# Demo_PCB.net
KiCad netlist of a schematic drawn in EAGLE
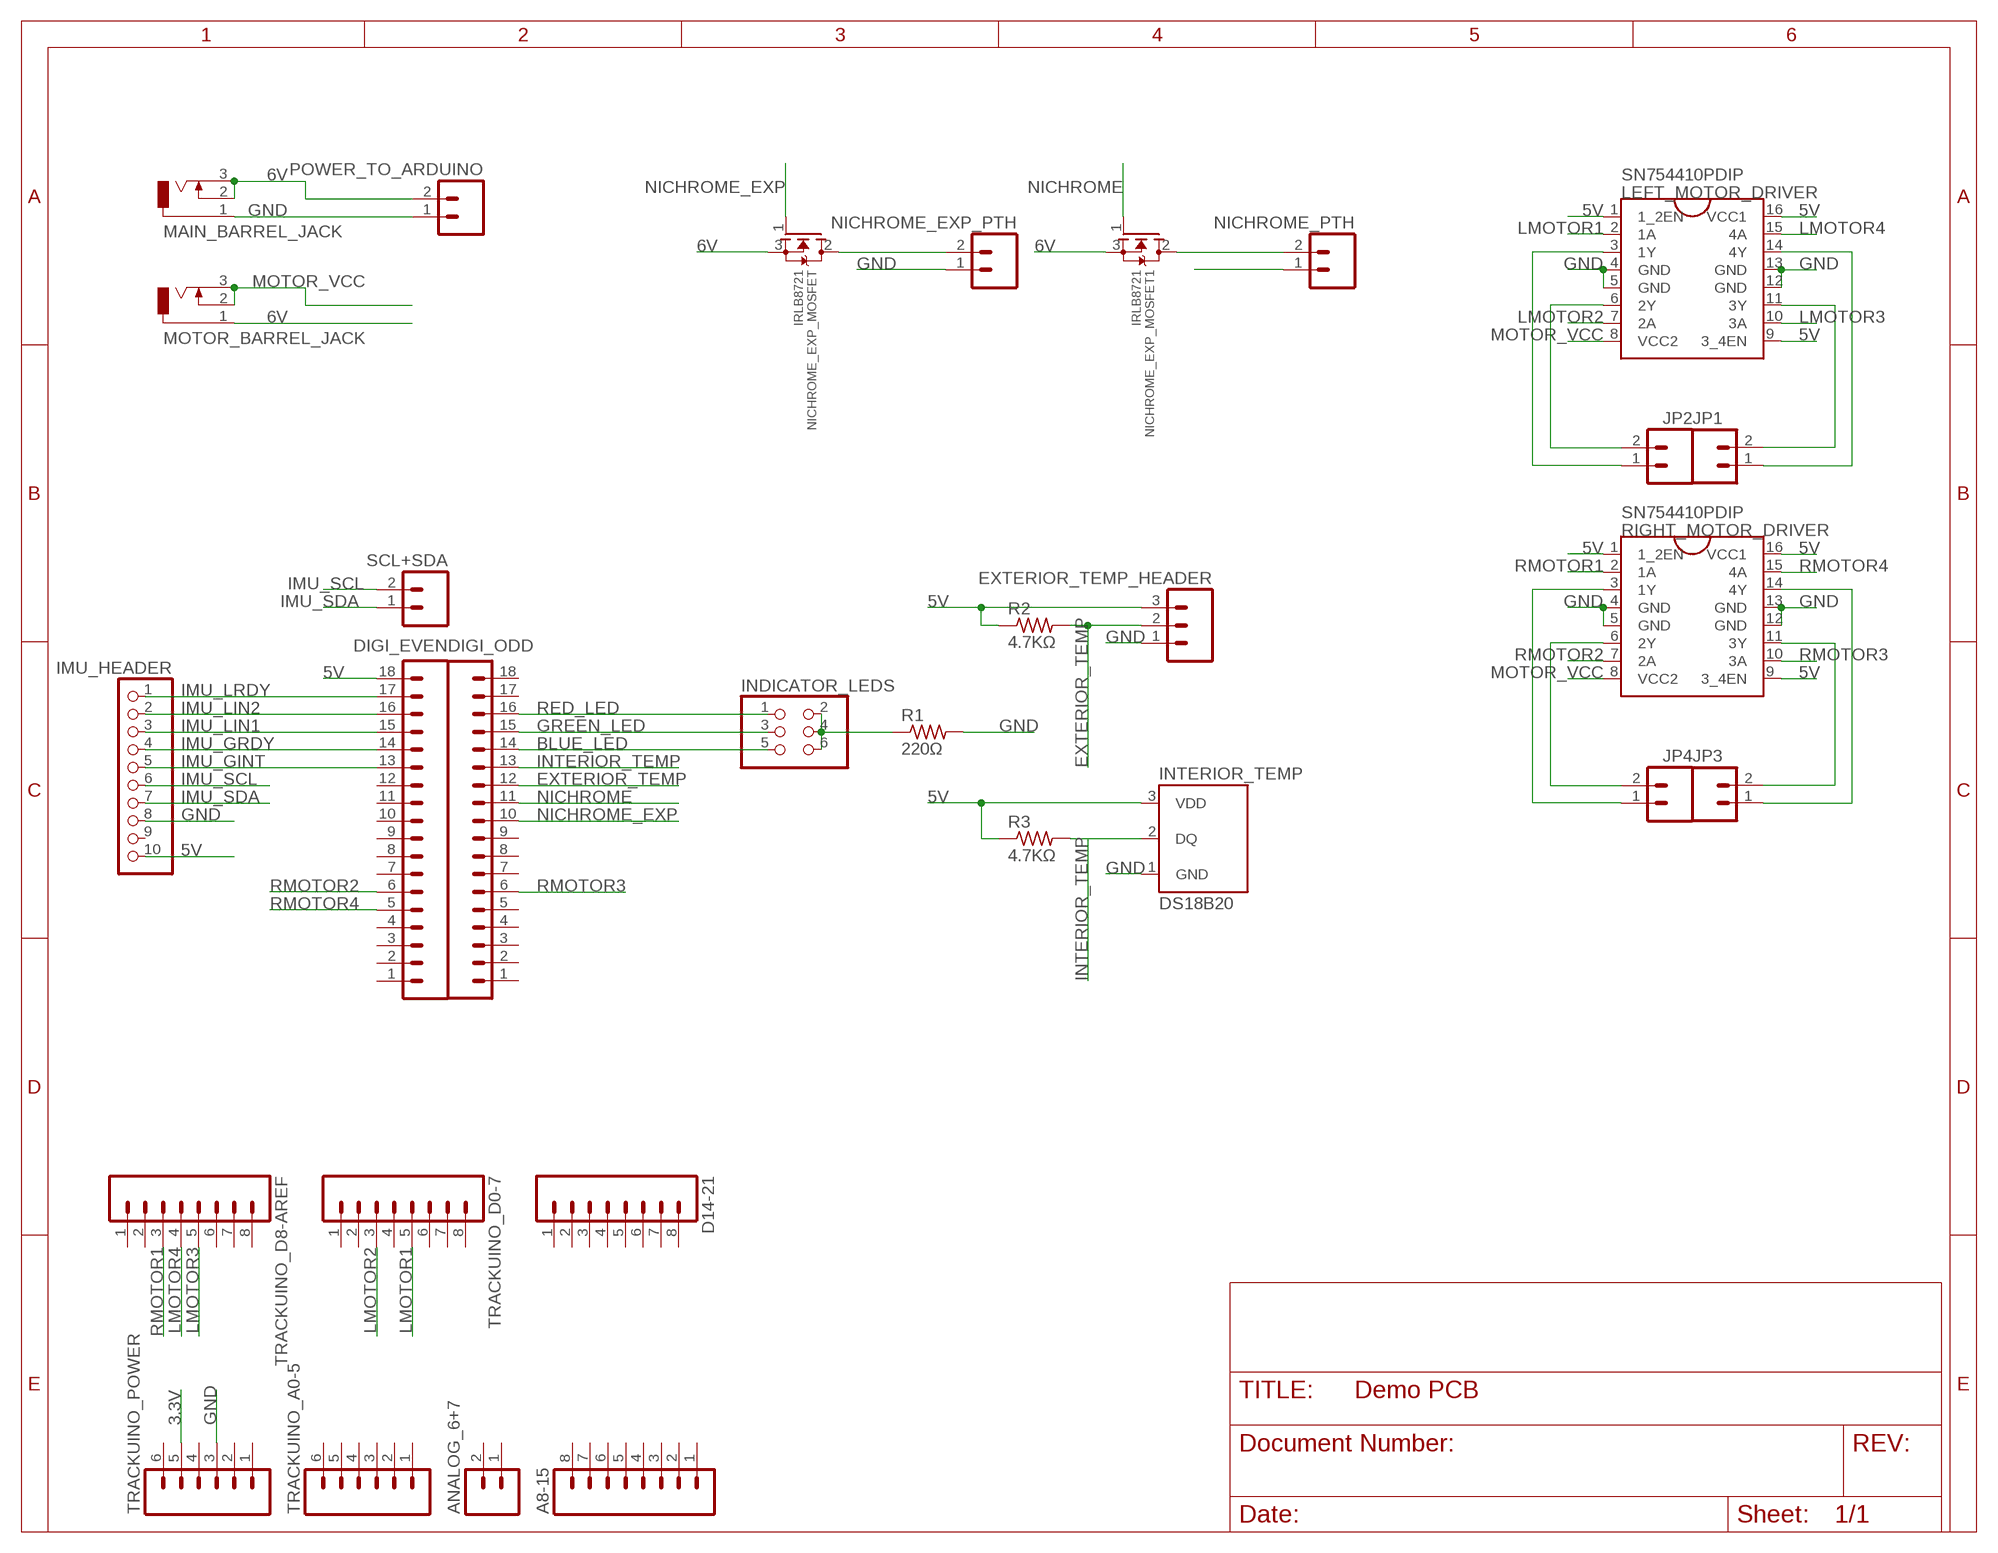
[diagram p0: schematic, sheet 1]

(export (version "E")
  (design (tool "Eeschema 10.0.6"))
  (components
    (comp (ref "A8-15")
      (value "M08")
      (footprint "eagle-import:1X08_ROUND")
      (libsource (lib "eagle-import") (part "M08"))
    )
    (comp (ref "ANALOG_6+7")
      (value "M02PTH")
      (footprint "eagle-import:1X02")
      (libsource (lib "eagle-import") (part "M02PTH"))
    )
    (comp (ref "D14-21")
      (value "M08")
      (footprint "eagle-import:1X08_ROUND")
      (libsource (lib "eagle-import") (part "M08"))
    )
    (comp (ref "DIGI_EVEN")
      (value "M18_")
      (footprint "eagle-import:1X18")
      (libsource (lib "eagle-import") (part "M18_"))
    )
    (comp (ref "DIGI_ODD")
      (value "M18_")
      (footprint "eagle-import:1X18")
      (libsource (lib "eagle-import") (part "M18_"))
    )
    (comp (ref "EXTERIOR_TEMP_HEADER")
      (value "M03PTH")
      (footprint "eagle-import:1X03")
      (libsource (lib "eagle-import") (part "M03PTH"))
    )
    (comp (ref "IMU_HEADER")
      (value "PINHD-1X10")
      (footprint "eagle-import:1X10")
      (libsource (lib "eagle-import") (part "PINHD-1X10"))
    )
    (comp (ref "INDICATOR_LEDS")
      (value "PINHD-2X3")
      (footprint "eagle-import:2X03")
      (libsource (lib "eagle-import") (part "PINHD-2X3"))
    )
    (comp (ref "INTERIOR_TEMP")
      (value "DS18B20")
      (footprint "eagle-import:TO-92-AMMO")
      (libsource (lib "eagle-import") (part "DS18B20"))
    )
    (comp (ref "JP1")
      (value "M02PTH")
      (footprint "eagle-import:1X02")
      (libsource (lib "eagle-import") (part "M02PTH"))
    )
    (comp (ref "JP2")
      (value "M02PTH")
      (footprint "eagle-import:1X02")
      (libsource (lib "eagle-import") (part "M02PTH"))
    )
    (comp (ref "JP3")
      (value "M02PTH")
      (footprint "eagle-import:1X02")
      (libsource (lib "eagle-import") (part "M02PTH"))
    )
    (comp (ref "JP4")
      (value "M02PTH")
      (footprint "eagle-import:1X02")
      (libsource (lib "eagle-import") (part "M02PTH"))
    )
    (comp (ref "LEFT_MOTOR_DRIVER")
      (value "SN754410PDIP")
      (footprint "eagle-import:DIL16")
      (libsource (lib "eagle-import") (part "SN754410PDIP"))
    )
    (comp (ref "MAIN_BARREL_JACK")
      (value "DCJ0303")
      (footprint "eagle-import:DCJ0303")
      (libsource (lib "eagle-import") (part "DCJ0303"))
    )
    (comp (ref "MOTOR_BARREL_JACK")
      (value "DCJ0303")
      (footprint "eagle-import:DCJ0303")
      (libsource (lib "eagle-import") (part "DCJ0303"))
    )
    (comp (ref "NICHROME_EXP_MOSFET")
      (value "IRLB8721")
      (footprint "eagle-import:TO220V")
      (libsource (lib "eagle-import") (part "MOSFET-NGDS_TO220V"))
    )
    (comp (ref "NICHROME_EXP_MOSFET1")
      (value "IRLB8721")
      (footprint "eagle-import:TO220V")
      (libsource (lib "eagle-import") (part "MOSFET-NGDS_TO220V"))
    )
    (comp (ref "NICHROME_EXP_PTH")
      (value "M02PTH")
      (footprint "eagle-import:1X02")
      (libsource (lib "eagle-import") (part "M02PTH"))
    )
    (comp (ref "NICHROME_PTH")
      (value "M02PTH")
      (footprint "eagle-import:1X02")
      (libsource (lib "eagle-import") (part "M02PTH"))
    )
    (comp (ref "POWER_TO_ARDUINO")
      (value "M02PTH")
      (footprint "eagle-import:1X02")
      (libsource (lib "eagle-import") (part "M02PTH"))
    )
    (comp (ref "R1")
      (value "220Ω")
      (footprint "eagle-import:0204_7")
      (libsource (lib "eagle-import") (part "R-US_0204/7"))
    )
    (comp (ref "R2")
      (value "4.7KΩ")
      (footprint "eagle-import:0204_7")
      (libsource (lib "eagle-import") (part "R-US_0204/7"))
    )
    (comp (ref "R3")
      (value "4.7KΩ")
      (footprint "eagle-import:0204_7")
      (libsource (lib "eagle-import") (part "R-US_0204/7"))
    )
    (comp (ref "RIGHT_MOTOR_DRIVER")
      (value "SN754410PDIP")
      (footprint "eagle-import:DIL16")
      (libsource (lib "eagle-import") (part "SN754410PDIP"))
    )
    (comp (ref "SCL+SDA")
      (value "M02PTH")
      (footprint "eagle-import:1X02")
      (libsource (lib "eagle-import") (part "M02PTH"))
    )
    (comp (ref "TRACKUINO_A0-5")
      (value "M06SILK_FEMALE_PTH")
      (footprint "eagle-import:1X06")
      (libsource (lib "eagle-import") (part "M06SILK_FEMALE_PTH"))
    )
    (comp (ref "TRACKUINO_D0-7")
      (value "M08")
      (footprint "eagle-import:1X08_ROUND")
      (libsource (lib "eagle-import") (part "M08"))
    )
    (comp (ref "TRACKUINO_D8-AREF")
      (value "M08")
      (footprint "eagle-import:1X08_ROUND")
      (libsource (lib "eagle-import") (part "M08"))
    )
    (comp (ref "TRACKUINO_POWER")
      (value "M06SILK_FEMALE_PTH")
      (footprint "eagle-import:1X06")
      (libsource (lib "eagle-import") (part "M06SILK_FEMALE_PTH"))
    )
  )
  (nets
    (net (code "1") (name "/3.3V") (class "Default")
      (node (ref "TRACKUINO_POWER") (pin "5") (pinfunction "5_5") (pintype "passive"))
    )
    (net (code "2") (name "/5V") (class "Default")
      (node (ref "DIGI_EVEN") (pin "18") (pinfunction "18_18") (pintype "passive"))
      (node (ref "EXTERIOR_TEMP_HEADER") (pin "3") (pinfunction "3_3") (pintype "passive"))
      (node (ref "IMU_HEADER") (pin "10") (pinfunction "10_10") (pintype "passive"))
      (node (ref "INTERIOR_TEMP") (pin "3") (pinfunction "VDD_3") (pintype "power_in"))
      (node (ref "LEFT_MOTOR_DRIVER") (pin "1") (pinfunction "1_2EN_1") (pintype "bidirectional"))
      (node (ref "LEFT_MOTOR_DRIVER") (pin "16") (pinfunction "VCC1_16") (pintype "bidirectional"))
      (node (ref "LEFT_MOTOR_DRIVER") (pin "9") (pinfunction "3_4EN_9") (pintype "bidirectional"))
      (node (ref "R2") (pin "1") (pinfunction "1_1") (pintype "passive"))
      (node (ref "R3") (pin "1") (pinfunction "1_1") (pintype "passive"))
      (node (ref "RIGHT_MOTOR_DRIVER") (pin "1") (pinfunction "1_2EN_1") (pintype "bidirectional"))
      (node (ref "RIGHT_MOTOR_DRIVER") (pin "16") (pinfunction "VCC1_16") (pintype "bidirectional"))
      (node (ref "RIGHT_MOTOR_DRIVER") (pin "9") (pinfunction "3_4EN_9") (pintype "bidirectional"))
    )
    (net (code "3") (name "/6V") (class "Default")
      (node (ref "MAIN_BARREL_JACK") (pin "2") (pinfunction "2_2") (pintype "passive"))
      (node (ref "MAIN_BARREL_JACK") (pin "3") (pinfunction "3_3") (pintype "passive"))
      (node (ref "MOTOR_BARREL_JACK") (pin "1") (pinfunction "1_1") (pintype "passive"))
      (node (ref "NICHROME_EXP_MOSFET") (pin "3") (pinfunction "S_3") (pintype "bidirectional"))
      (node (ref "NICHROME_EXP_MOSFET1") (pin "3") (pinfunction "S_3") (pintype "bidirectional"))
      (node (ref "POWER_TO_ARDUINO") (pin "2") (pinfunction "2_2") (pintype "passive"))
    )
    (net (code "4") (name "/BLUE_LED") (class "Default")
      (node (ref "DIGI_ODD") (pin "14") (pinfunction "14_14") (pintype "passive"))
      (node (ref "INDICATOR_LEDS") (pin "5") (pinfunction "5_5") (pintype "passive"))
    )
    (net (code "5") (name "/EXTERIOR_TEMP") (class "Default")
      (node (ref "DIGI_ODD") (pin "12") (pinfunction "12_12") (pintype "passive"))
      (node (ref "EXTERIOR_TEMP_HEADER") (pin "2") (pinfunction "2_2") (pintype "passive"))
      (node (ref "R2") (pin "2") (pinfunction "2_2") (pintype "passive"))
    )
    (net (code "6") (name "/GND") (class "Default")
      (node (ref "EXTERIOR_TEMP_HEADER") (pin "1") (pinfunction "1_1") (pintype "passive"))
      (node (ref "IMU_HEADER") (pin "8") (pinfunction "8_8") (pintype "passive"))
      (node (ref "INTERIOR_TEMP") (pin "1") (pinfunction "GND_1") (pintype "power_in"))
      (node (ref "LEFT_MOTOR_DRIVER") (pin "12") (pinfunction "GND_12") (pintype "bidirectional"))
      (node (ref "LEFT_MOTOR_DRIVER") (pin "13") (pinfunction "GND_13") (pintype "bidirectional"))
      (node (ref "LEFT_MOTOR_DRIVER") (pin "4") (pinfunction "GND_4") (pintype "bidirectional"))
      (node (ref "LEFT_MOTOR_DRIVER") (pin "5") (pinfunction "GND_5") (pintype "bidirectional"))
      (node (ref "MAIN_BARREL_JACK") (pin "1") (pinfunction "1_1") (pintype "passive"))
      (node (ref "NICHROME_EXP_PTH") (pin "1") (pinfunction "1_1") (pintype "passive"))
      (node (ref "NICHROME_PTH") (pin "1") (pinfunction "1_1") (pintype "passive"))
      (node (ref "POWER_TO_ARDUINO") (pin "1") (pinfunction "1_1") (pintype "passive"))
      (node (ref "R1") (pin "2") (pinfunction "2_2") (pintype "passive"))
      (node (ref "RIGHT_MOTOR_DRIVER") (pin "12") (pinfunction "GND_12") (pintype "bidirectional"))
      (node (ref "RIGHT_MOTOR_DRIVER") (pin "13") (pinfunction "GND_13") (pintype "bidirectional"))
      (node (ref "RIGHT_MOTOR_DRIVER") (pin "4") (pinfunction "GND_4") (pintype "bidirectional"))
      (node (ref "RIGHT_MOTOR_DRIVER") (pin "5") (pinfunction "GND_5") (pintype "bidirectional"))
      (node (ref "TRACKUINO_POWER") (pin "3") (pinfunction "3_3") (pintype "passive"))
    )
    (net (code "7") (name "/GREEN_LED") (class "Default")
      (node (ref "DIGI_ODD") (pin "15") (pinfunction "15_15") (pintype "passive"))
      (node (ref "INDICATOR_LEDS") (pin "3") (pinfunction "3_3") (pintype "passive"))
    )
    (net (code "8") (name "/IMU_GINT") (class "Default")
      (node (ref "DIGI_EVEN") (pin "13") (pinfunction "13_13") (pintype "passive"))
      (node (ref "IMU_HEADER") (pin "5") (pinfunction "5_5") (pintype "passive"))
    )
    (net (code "9") (name "/IMU_GRDY") (class "Default")
      (node (ref "DIGI_EVEN") (pin "14") (pinfunction "14_14") (pintype "passive"))
      (node (ref "IMU_HEADER") (pin "4") (pinfunction "4_4") (pintype "passive"))
    )
    (net (code "10") (name "/IMU_LIN1") (class "Default")
      (node (ref "DIGI_EVEN") (pin "15") (pinfunction "15_15") (pintype "passive"))
      (node (ref "IMU_HEADER") (pin "3") (pinfunction "3_3") (pintype "passive"))
    )
    (net (code "11") (name "/IMU_LIN2") (class "Default")
      (node (ref "DIGI_EVEN") (pin "16") (pinfunction "16_16") (pintype "passive"))
      (node (ref "IMU_HEADER") (pin "2") (pinfunction "2_2") (pintype "passive"))
    )
    (net (code "12") (name "/IMU_LRDY") (class "Default")
      (node (ref "DIGI_EVEN") (pin "17") (pinfunction "17_17") (pintype "passive"))
      (node (ref "IMU_HEADER") (pin "1") (pinfunction "1_1") (pintype "passive"))
    )
    (net (code "13") (name "/IMU_SCL") (class "Default")
      (node (ref "IMU_HEADER") (pin "6") (pinfunction "6_6") (pintype "passive"))
      (node (ref "SCL+SDA") (pin "2") (pinfunction "2_2") (pintype "passive"))
    )
    (net (code "14") (name "/IMU_SDA") (class "Default")
      (node (ref "IMU_HEADER") (pin "7") (pinfunction "7_7") (pintype "passive"))
      (node (ref "SCL+SDA") (pin "1") (pinfunction "1_1") (pintype "passive"))
    )
    (net (code "15") (name "/INTERIOR_TEMP") (class "Default")
      (node (ref "DIGI_ODD") (pin "13") (pinfunction "13_13") (pintype "passive"))
    )
    (net (code "16") (name "/LMOTOR1") (class "Default")
      (node (ref "LEFT_MOTOR_DRIVER") (pin "2") (pinfunction "1A_2") (pintype "bidirectional"))
      (node (ref "TRACKUINO_D0-7") (pin "5") (pinfunction "5_5") (pintype "passive"))
    )
    (net (code "17") (name "/LMOTOR2") (class "Default")
      (node (ref "LEFT_MOTOR_DRIVER") (pin "7") (pinfunction "2A_7") (pintype "bidirectional"))
      (node (ref "TRACKUINO_D0-7") (pin "3") (pinfunction "3_3") (pintype "passive"))
    )
    (net (code "18") (name "/LMOTOR3") (class "Default")
      (node (ref "LEFT_MOTOR_DRIVER") (pin "10") (pinfunction "3A_10") (pintype "bidirectional"))
      (node (ref "TRACKUINO_D8-AREF") (pin "5") (pinfunction "5_5") (pintype "passive"))
    )
    (net (code "19") (name "/LMOTOR4") (class "Default")
      (node (ref "LEFT_MOTOR_DRIVER") (pin "15") (pinfunction "4A_15") (pintype "bidirectional"))
      (node (ref "TRACKUINO_D8-AREF") (pin "4") (pinfunction "4_4") (pintype "passive"))
    )
    (net (code "20") (name "/MOTOR_VCC") (class "Default")
      (node (ref "LEFT_MOTOR_DRIVER") (pin "8") (pinfunction "VCC2_8") (pintype "bidirectional"))
      (node (ref "MOTOR_BARREL_JACK") (pin "2") (pinfunction "2_2") (pintype "passive"))
      (node (ref "MOTOR_BARREL_JACK") (pin "3") (pinfunction "3_3") (pintype "passive"))
      (node (ref "RIGHT_MOTOR_DRIVER") (pin "8") (pinfunction "VCC2_8") (pintype "bidirectional"))
    )
    (net (code "21") (name "/N$2") (class "Default")
      (node (ref "NICHROME_EXP_MOSFET") (pin "2") (pinfunction "D_2") (pintype "bidirectional"))
      (node (ref "NICHROME_EXP_MOSFET1") (pin "2") (pinfunction "D_2") (pintype "bidirectional"))
      (node (ref "NICHROME_EXP_PTH") (pin "2") (pinfunction "2_2") (pintype "passive"))
      (node (ref "NICHROME_PTH") (pin "2") (pinfunction "2_2") (pintype "passive"))
    )
    (net (code "22") (name "/NICHROME") (class "Default")
      (node (ref "DIGI_ODD") (pin "11") (pinfunction "11_11") (pintype "passive"))
      (node (ref "NICHROME_EXP_MOSFET1") (pin "1") (pinfunction "G_1") (pintype "bidirectional"))
    )
    (net (code "23") (name "/NICHROME_EXP") (class "Default")
      (node (ref "DIGI_ODD") (pin "10") (pinfunction "10_10") (pintype "passive"))
      (node (ref "NICHROME_EXP_MOSFET") (pin "1") (pinfunction "G_1") (pintype "bidirectional"))
    )
    (net (code "24") (name "/RED_LED") (class "Default")
      (node (ref "DIGI_ODD") (pin "16") (pinfunction "16_16") (pintype "passive"))
      (node (ref "INDICATOR_LEDS") (pin "1") (pinfunction "1_1") (pintype "passive"))
    )
    (net (code "25") (name "/RMOTOR1") (class "Default")
      (node (ref "RIGHT_MOTOR_DRIVER") (pin "2") (pinfunction "1A_2") (pintype "bidirectional"))
      (node (ref "TRACKUINO_D8-AREF") (pin "3") (pinfunction "3_3") (pintype "passive"))
    )
    (net (code "26") (name "/RMOTOR2") (class "Default")
      (node (ref "DIGI_EVEN") (pin "6") (pinfunction "6_6") (pintype "passive"))
      (node (ref "RIGHT_MOTOR_DRIVER") (pin "7") (pinfunction "2A_7") (pintype "bidirectional"))
    )
    (net (code "27") (name "/RMOTOR3") (class "Default")
      (node (ref "DIGI_ODD") (pin "6") (pinfunction "6_6") (pintype "passive"))
      (node (ref "RIGHT_MOTOR_DRIVER") (pin "10") (pinfunction "3A_10") (pintype "bidirectional"))
    )
    (net (code "28") (name "/RMOTOR4") (class "Default")
      (node (ref "DIGI_EVEN") (pin "5") (pinfunction "5_5") (pintype "passive"))
      (node (ref "RIGHT_MOTOR_DRIVER") (pin "15") (pinfunction "4A_15") (pintype "bidirectional"))
    )
    (net (code "29") (name "Net-(INDICATOR_LEDS-Pad2)") (class "Default")
      (node (ref "INDICATOR_LEDS") (pin "2") (pinfunction "2_2") (pintype "passive"))
      (node (ref "INDICATOR_LEDS") (pin "4") (pinfunction "4_4") (pintype "passive"))
      (node (ref "INDICATOR_LEDS") (pin "6") (pinfunction "6_6") (pintype "passive"))
      (node (ref "R1") (pin "1") (pinfunction "1_1") (pintype "passive"))
    )
    (net (code "30") (name "Net-(INTERIOR_TEMP-DQ)") (class "Default")
      (node (ref "INTERIOR_TEMP") (pin "2") (pinfunction "DQ_2") (pintype "bidirectional"))
      (node (ref "R3") (pin "2") (pinfunction "2_2") (pintype "passive"))
    )
    (net (code "31") (name "Net-(LEFT_MOTOR_DRIVER-1Y)") (class "Default")
      (node (ref "JP2") (pin "1") (pinfunction "1_1") (pintype "passive"))
      (node (ref "LEFT_MOTOR_DRIVER") (pin "3") (pinfunction "1Y_3") (pintype "bidirectional"))
    )
    (net (code "32") (name "Net-(LEFT_MOTOR_DRIVER-2Y)") (class "Default")
      (node (ref "JP2") (pin "2") (pinfunction "2_2") (pintype "passive"))
      (node (ref "LEFT_MOTOR_DRIVER") (pin "6") (pinfunction "2Y_6") (pintype "bidirectional"))
    )
    (net (code "33") (name "Net-(LEFT_MOTOR_DRIVER-3Y)") (class "Default")
      (node (ref "JP1") (pin "2") (pinfunction "2_2") (pintype "passive"))
      (node (ref "LEFT_MOTOR_DRIVER") (pin "11") (pinfunction "3Y_11") (pintype "bidirectional"))
    )
    (net (code "34") (name "Net-(LEFT_MOTOR_DRIVER-4Y)") (class "Default")
      (node (ref "JP1") (pin "1") (pinfunction "1_1") (pintype "passive"))
      (node (ref "LEFT_MOTOR_DRIVER") (pin "14") (pinfunction "4Y_14") (pintype "bidirectional"))
    )
    (net (code "35") (name "Net-(RIGHT_MOTOR_DRIVER-1Y)") (class "Default")
      (node (ref "JP4") (pin "1") (pinfunction "1_1") (pintype "passive"))
      (node (ref "RIGHT_MOTOR_DRIVER") (pin "3") (pinfunction "1Y_3") (pintype "bidirectional"))
    )
    (net (code "36") (name "Net-(RIGHT_MOTOR_DRIVER-2Y)") (class "Default")
      (node (ref "JP4") (pin "2") (pinfunction "2_2") (pintype "passive"))
      (node (ref "RIGHT_MOTOR_DRIVER") (pin "6") (pinfunction "2Y_6") (pintype "bidirectional"))
    )
    (net (code "37") (name "Net-(RIGHT_MOTOR_DRIVER-3Y)") (class "Default")
      (node (ref "JP3") (pin "2") (pinfunction "2_2") (pintype "passive"))
      (node (ref "RIGHT_MOTOR_DRIVER") (pin "11") (pinfunction "3Y_11") (pintype "bidirectional"))
    )
    (net (code "38") (name "Net-(RIGHT_MOTOR_DRIVER-4Y)") (class "Default")
      (node (ref "JP3") (pin "1") (pinfunction "1_1") (pintype "passive"))
      (node (ref "RIGHT_MOTOR_DRIVER") (pin "14") (pinfunction "4Y_14") (pintype "bidirectional"))
    )
    (net (code "39") (name "unconnected-(A8-15-Pad1)") (class "Default")
      (node (ref "A8-15") (pin "1") (pinfunction "1_1") (pintype "passive"))
    )
    (net (code "40") (name "unconnected-(A8-15-Pad2)") (class "Default")
      (node (ref "A8-15") (pin "2") (pinfunction "2_2") (pintype "passive"))
    )
    (net (code "41") (name "unconnected-(A8-15-Pad3)") (class "Default")
      (node (ref "A8-15") (pin "3") (pinfunction "3_3") (pintype "passive"))
    )
    (net (code "42") (name "unconnected-(A8-15-Pad4)") (class "Default")
      (node (ref "A8-15") (pin "4") (pinfunction "4_4") (pintype "passive"))
    )
    (net (code "43") (name "unconnected-(A8-15-Pad5)") (class "Default")
      (node (ref "A8-15") (pin "5") (pinfunction "5_5") (pintype "passive"))
    )
    (net (code "44") (name "unconnected-(A8-15-Pad6)") (class "Default")
      (node (ref "A8-15") (pin "6") (pinfunction "6_6") (pintype "passive"))
    )
    (net (code "45") (name "unconnected-(A8-15-Pad7)") (class "Default")
      (node (ref "A8-15") (pin "7") (pinfunction "7_7") (pintype "passive"))
    )
    (net (code "46") (name "unconnected-(A8-15-Pad8)") (class "Default")
      (node (ref "A8-15") (pin "8") (pinfunction "8_8") (pintype "passive"))
    )
    (net (code "47") (name "unconnected-(ANALOG_6+7-Pad1)") (class "Default")
      (node (ref "ANALOG_6+7") (pin "1") (pinfunction "1_1") (pintype "passive"))
    )
    (net (code "48") (name "unconnected-(ANALOG_6+7-Pad2)") (class "Default")
      (node (ref "ANALOG_6+7") (pin "2") (pinfunction "2_2") (pintype "passive"))
    )
    (net (code "49") (name "unconnected-(D14-21-Pad1)") (class "Default")
      (node (ref "D14-21") (pin "1") (pinfunction "1_1") (pintype "passive"))
    )
    (net (code "50") (name "unconnected-(D14-21-Pad2)") (class "Default")
      (node (ref "D14-21") (pin "2") (pinfunction "2_2") (pintype "passive"))
    )
    (net (code "51") (name "unconnected-(D14-21-Pad3)") (class "Default")
      (node (ref "D14-21") (pin "3") (pinfunction "3_3") (pintype "passive"))
    )
    (net (code "52") (name "unconnected-(D14-21-Pad4)") (class "Default")
      (node (ref "D14-21") (pin "4") (pinfunction "4_4") (pintype "passive"))
    )
    (net (code "53") (name "unconnected-(D14-21-Pad5)") (class "Default")
      (node (ref "D14-21") (pin "5") (pinfunction "5_5") (pintype "passive"))
    )
    (net (code "54") (name "unconnected-(D14-21-Pad6)") (class "Default")
      (node (ref "D14-21") (pin "6") (pinfunction "6_6") (pintype "passive"))
    )
    (net (code "55") (name "unconnected-(D14-21-Pad7)") (class "Default")
      (node (ref "D14-21") (pin "7") (pinfunction "7_7") (pintype "passive"))
    )
    (net (code "56") (name "unconnected-(D14-21-Pad8)") (class "Default")
      (node (ref "D14-21") (pin "8") (pinfunction "8_8") (pintype "passive"))
    )
    (net (code "57") (name "unconnected-(DIGI_EVEN-Pad1)") (class "Default")
      (node (ref "DIGI_EVEN") (pin "1") (pinfunction "1_1") (pintype "passive"))
    )
    (net (code "58") (name "unconnected-(DIGI_EVEN-Pad2)") (class "Default")
      (node (ref "DIGI_EVEN") (pin "2") (pinfunction "2_2") (pintype "passive"))
    )
    (net (code "59") (name "unconnected-(DIGI_EVEN-Pad3)") (class "Default")
      (node (ref "DIGI_EVEN") (pin "3") (pinfunction "3_3") (pintype "passive"))
    )
    (net (code "60") (name "unconnected-(DIGI_EVEN-Pad4)") (class "Default")
      (node (ref "DIGI_EVEN") (pin "4") (pinfunction "4_4") (pintype "passive"))
    )
    (net (code "61") (name "unconnected-(DIGI_EVEN-Pad7)") (class "Default")
      (node (ref "DIGI_EVEN") (pin "7") (pinfunction "7_7") (pintype "passive"))
    )
    (net (code "62") (name "unconnected-(DIGI_EVEN-Pad8)") (class "Default")
      (node (ref "DIGI_EVEN") (pin "8") (pinfunction "8_8") (pintype "passive"))
    )
    (net (code "63") (name "unconnected-(DIGI_EVEN-Pad9)") (class "Default")
      (node (ref "DIGI_EVEN") (pin "9") (pinfunction "9_9") (pintype "passive"))
    )
    (net (code "64") (name "unconnected-(DIGI_EVEN-Pad10)") (class "Default")
      (node (ref "DIGI_EVEN") (pin "10") (pinfunction "10_10") (pintype "passive"))
    )
    (net (code "65") (name "unconnected-(DIGI_EVEN-Pad11)") (class "Default")
      (node (ref "DIGI_EVEN") (pin "11") (pinfunction "11_11") (pintype "passive"))
    )
    (net (code "66") (name "unconnected-(DIGI_EVEN-Pad12)") (class "Default")
      (node (ref "DIGI_EVEN") (pin "12") (pinfunction "12_12") (pintype "passive"))
    )
    (net (code "67") (name "unconnected-(DIGI_ODD-Pad1)") (class "Default")
      (node (ref "DIGI_ODD") (pin "1") (pinfunction "1_1") (pintype "passive"))
    )
    (net (code "68") (name "unconnected-(DIGI_ODD-Pad2)") (class "Default")
      (node (ref "DIGI_ODD") (pin "2") (pinfunction "2_2") (pintype "passive"))
    )
    (net (code "69") (name "unconnected-(DIGI_ODD-Pad3)") (class "Default")
      (node (ref "DIGI_ODD") (pin "3") (pinfunction "3_3") (pintype "passive"))
    )
    (net (code "70") (name "unconnected-(DIGI_ODD-Pad4)") (class "Default")
      (node (ref "DIGI_ODD") (pin "4") (pinfunction "4_4") (pintype "passive"))
    )
    (net (code "71") (name "unconnected-(DIGI_ODD-Pad5)") (class "Default")
      (node (ref "DIGI_ODD") (pin "5") (pinfunction "5_5") (pintype "passive"))
    )
    (net (code "72") (name "unconnected-(DIGI_ODD-Pad7)") (class "Default")
      (node (ref "DIGI_ODD") (pin "7") (pinfunction "7_7") (pintype "passive"))
    )
    (net (code "73") (name "unconnected-(DIGI_ODD-Pad8)") (class "Default")
      (node (ref "DIGI_ODD") (pin "8") (pinfunction "8_8") (pintype "passive"))
    )
    (net (code "74") (name "unconnected-(DIGI_ODD-Pad9)") (class "Default")
      (node (ref "DIGI_ODD") (pin "9") (pinfunction "9_9") (pintype "passive"))
    )
    (net (code "75") (name "unconnected-(DIGI_ODD-Pad17)") (class "Default")
      (node (ref "DIGI_ODD") (pin "17") (pinfunction "17_17") (pintype "passive"))
    )
    (net (code "76") (name "unconnected-(DIGI_ODD-Pad18)") (class "Default")
      (node (ref "DIGI_ODD") (pin "18") (pinfunction "18_18") (pintype "passive"))
    )
    (net (code "77") (name "unconnected-(IMU_HEADER-Pad9)") (class "Default")
      (node (ref "IMU_HEADER") (pin "9") (pinfunction "9_9") (pintype "passive"))
    )
    (net (code "78") (name "unconnected-(TRACKUINO_A0-5-Pad1)") (class "Default")
      (node (ref "TRACKUINO_A0-5") (pin "1") (pinfunction "1_1") (pintype "passive"))
    )
    (net (code "79") (name "unconnected-(TRACKUINO_A0-5-Pad2)") (class "Default")
      (node (ref "TRACKUINO_A0-5") (pin "2") (pinfunction "2_2") (pintype "passive"))
    )
    (net (code "80") (name "unconnected-(TRACKUINO_A0-5-Pad3)") (class "Default")
      (node (ref "TRACKUINO_A0-5") (pin "3") (pinfunction "3_3") (pintype "passive"))
    )
    (net (code "81") (name "unconnected-(TRACKUINO_A0-5-Pad4)") (class "Default")
      (node (ref "TRACKUINO_A0-5") (pin "4") (pinfunction "4_4") (pintype "passive"))
    )
    (net (code "82") (name "unconnected-(TRACKUINO_A0-5-Pad5)") (class "Default")
      (node (ref "TRACKUINO_A0-5") (pin "5") (pinfunction "5_5") (pintype "passive"))
    )
    (net (code "83") (name "unconnected-(TRACKUINO_A0-5-Pad6)") (class "Default")
      (node (ref "TRACKUINO_A0-5") (pin "6") (pinfunction "6_6") (pintype "passive"))
    )
    (net (code "84") (name "unconnected-(TRACKUINO_D0-7-Pad1)") (class "Default")
      (node (ref "TRACKUINO_D0-7") (pin "1") (pinfunction "1_1") (pintype "passive"))
    )
    (net (code "85") (name "unconnected-(TRACKUINO_D0-7-Pad2)") (class "Default")
      (node (ref "TRACKUINO_D0-7") (pin "2") (pinfunction "2_2") (pintype "passive"))
    )
    (net (code "86") (name "unconnected-(TRACKUINO_D0-7-Pad4)") (class "Default")
      (node (ref "TRACKUINO_D0-7") (pin "4") (pinfunction "4_4") (pintype "passive"))
    )
    (net (code "87") (name "unconnected-(TRACKUINO_D0-7-Pad6)") (class "Default")
      (node (ref "TRACKUINO_D0-7") (pin "6") (pinfunction "6_6") (pintype "passive"))
    )
    (net (code "88") (name "unconnected-(TRACKUINO_D0-7-Pad7)") (class "Default")
      (node (ref "TRACKUINO_D0-7") (pin "7") (pinfunction "7_7") (pintype "passive"))
    )
    (net (code "89") (name "unconnected-(TRACKUINO_D0-7-Pad8)") (class "Default")
      (node (ref "TRACKUINO_D0-7") (pin "8") (pinfunction "8_8") (pintype "passive"))
    )
    (net (code "90") (name "unconnected-(TRACKUINO_D8-AREF-Pad1)") (class "Default")
      (node (ref "TRACKUINO_D8-AREF") (pin "1") (pinfunction "1_1") (pintype "passive"))
    )
    (net (code "91") (name "unconnected-(TRACKUINO_D8-AREF-Pad2)") (class "Default")
      (node (ref "TRACKUINO_D8-AREF") (pin "2") (pinfunction "2_2") (pintype "passive"))
    )
    (net (code "92") (name "unconnected-(TRACKUINO_D8-AREF-Pad6)") (class "Default")
      (node (ref "TRACKUINO_D8-AREF") (pin "6") (pinfunction "6_6") (pintype "passive"))
    )
    (net (code "93") (name "unconnected-(TRACKUINO_D8-AREF-Pad7)") (class "Default")
      (node (ref "TRACKUINO_D8-AREF") (pin "7") (pinfunction "7_7") (pintype "passive"))
    )
    (net (code "94") (name "unconnected-(TRACKUINO_D8-AREF-Pad8)") (class "Default")
      (node (ref "TRACKUINO_D8-AREF") (pin "8") (pinfunction "8_8") (pintype "passive"))
    )
    (net (code "95") (name "unconnected-(TRACKUINO_POWER-Pad1)") (class "Default")
      (node (ref "TRACKUINO_POWER") (pin "1") (pinfunction "1_1") (pintype "passive"))
    )
    (net (code "96") (name "unconnected-(TRACKUINO_POWER-Pad2)") (class "Default")
      (node (ref "TRACKUINO_POWER") (pin "2") (pinfunction "2_2") (pintype "passive"))
    )
    (net (code "97") (name "unconnected-(TRACKUINO_POWER-Pad4)") (class "Default")
      (node (ref "TRACKUINO_POWER") (pin "4") (pinfunction "4_4") (pintype "passive"))
    )
    (net (code "98") (name "unconnected-(TRACKUINO_POWER-Pad6)") (class "Default")
      (node (ref "TRACKUINO_POWER") (pin "6") (pinfunction "6_6") (pintype "passive"))
    )
  )
)
